# Motor_Control.net
KiCad netlist of a schematic drawn in Altium Designer
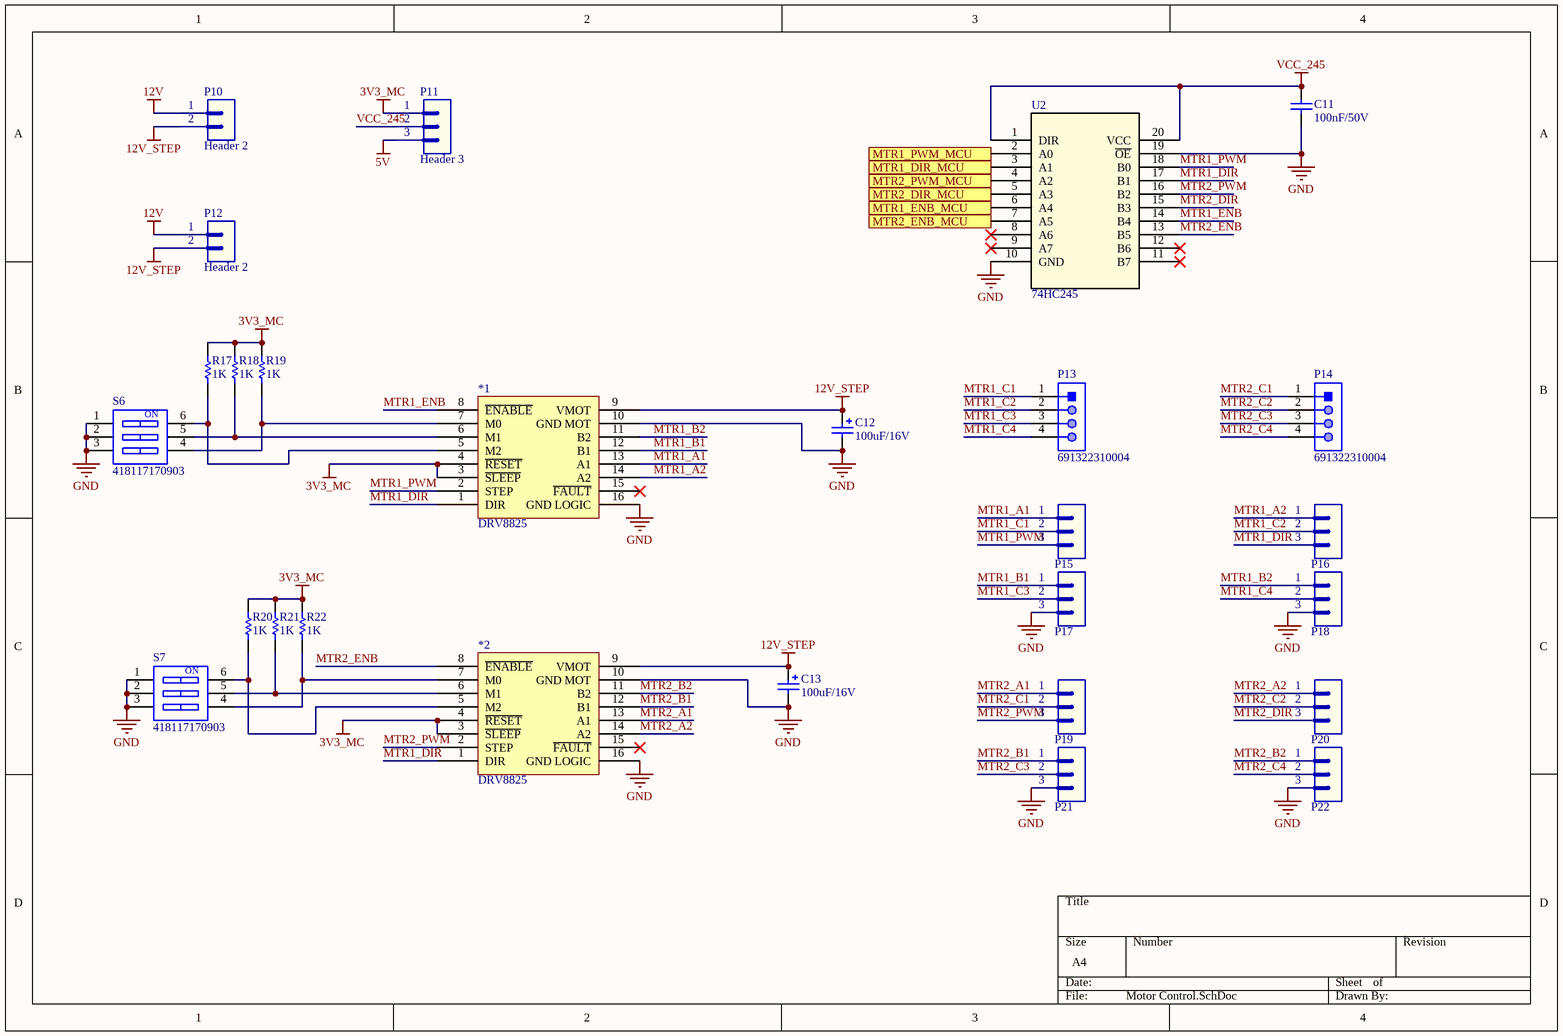
[diagram p0: Motor Control.SchDoc]

(export (version "E")
  (design (tool "Eeschema 10.0.6"))
  (components
    (comp (ref "*1")
      (value "DRV8825")
      (footprint "DRV8825")
      (libsource (lib "Integrated_Library") (part "DRV8825"))
    )
    (comp (ref "*2")
      (value "DRV8825")
      (footprint "DRV8825")
      (libsource (lib "Integrated_Library") (part "DRV8825"))
    )
    (comp (ref "C11")
      (value "100nF/50V")
      (footprint "CAP-SM-0805")
      (description "CAP CER 10UF 50V X5R 0805")
      (fields
        (field (name "MANUFACTURER") "Yageo")
        (field (name "MANUFACTURER PART NUMBER") "CC0805KKX5R9BB106")
      )
      (libsource (lib "Capacitor") (part "Cap-10uF-50V-0805"))
    )
    (comp (ref "C12")
      (value "100uF/16V")
      (footprint "CAP-SM-AL-SIZE-D-D6L6")
      (description "CAP ALUM 100UF 20% 16V SMD")
      (fields
        (field (name "MANUFACTURER") "Nichicon")
        (field (name "MANUFACTURER PART NUMBER") "UWX1C101MCL1GB")
      )
      (libsource (lib "Capacitor") (part "Cap-Al-100uF-16V-D6L5"))
    )
    (comp (ref "C13")
      (value "100uF/16V")
      (footprint "CAP-SM-AL-SIZE-D-D6L6")
      (description "CAP ALUM 100UF 20% 16V SMD")
      (fields
        (field (name "MANUFACTURER") "Nichicon")
        (field (name "MANUFACTURER PART NUMBER") "UWX1C101MCL1GB")
      )
      (libsource (lib "") (part "Cap-Al-100uF-16V-D6L5_1"))
    )
    (comp (ref "P10")
      (value "Header 2")
      (footprint "JP2")
      (description "Header, 2-Pin")
      (fields (field (name "PUBLISHER") "Altium Limited"))
      (libsource (lib "PIF_C16_lib") (part "Header 2"))
    )
    (comp (ref "P11")
      (value "Header 3")
      (footprint "JP3")
      (description "Header, 3-Pin")
      (fields (field (name "PUBLISHER") "Altium Limited"))
      (libsource (lib "PIF_C16_lib") (part "Header 3"))
    )
    (comp (ref "P12")
      (value "Header 2")
      (footprint "JP2")
      (description "Header, 2-Pin")
      (fields (field (name "PUBLISHER") "Altium Limited"))
      (libsource (lib "PIF_C16_lib") (part "Header 2"))
    )
    (comp (ref "P13")
      (value "691322310004")
      (footprint "691322310004")
      (description "WR-TBL Serie 322 Horizontal PCB Header, Pluggable, pitch 3.81mm, 4p")
      (fields (field (name "PUBLISHER") "Wurth Elektronik"))
      (libsource (lib "691101710002_Altium_WR-TBL_rev19a") (part "691322310004"))
    )
    (comp (ref "P14")
      (value "691322310004")
      (footprint "691322310004")
      (description "WR-TBL Serie 322 Horizontal PCB Header, Pluggable, pitch 3.81mm, 4p")
      (fields (field (name "PUBLISHER") "Wurth Elektronik"))
      (libsource (lib "691101710002_Altium_WR-TBL_rev19a") (part "691322310004"))
    )
    (comp (ref "P15")
      (value "Header 3")
      (footprint "JP3")
      (description "Header, 3-Pin")
      (fields (field (name "PUBLISHER") "Altium Limited"))
      (libsource (lib "Header-connector") (part "Header 3"))
    )
    (comp (ref "P16")
      (value "Header 3")
      (footprint "JP3")
      (description "Header, 3-Pin")
      (fields (field (name "PUBLISHER") "Altium Limited"))
      (libsource (lib "Header-connector") (part "Header 3"))
    )
    (comp (ref "P17")
      (value "Header 3")
      (footprint "JP3")
      (description "Header, 3-Pin")
      (fields (field (name "PUBLISHER") "Altium Limited"))
      (libsource (lib "Header-connector") (part "Header 3"))
    )
    (comp (ref "P18")
      (value "Header 3")
      (footprint "JP3")
      (description "Header, 3-Pin")
      (fields (field (name "PUBLISHER") "Altium Limited"))
      (libsource (lib "Header-connector") (part "Header 3"))
    )
    (comp (ref "P19")
      (value "Header 3")
      (footprint "JP3")
      (description "Header, 3-Pin")
      (fields (field (name "PUBLISHER") "Altium Limited"))
      (libsource (lib "Header-connector") (part "Header 3"))
    )
    (comp (ref "P20")
      (value "Header 3")
      (footprint "JP3")
      (description "Header, 3-Pin")
      (fields (field (name "PUBLISHER") "Altium Limited"))
      (libsource (lib "Header-connector") (part "Header 3"))
    )
    (comp (ref "P21")
      (value "Header 3")
      (footprint "JP3")
      (description "Header, 3-Pin")
      (fields (field (name "PUBLISHER") "Altium Limited"))
      (libsource (lib "Header-connector") (part "Header 3"))
    )
    (comp (ref "P22")
      (value "Header 3")
      (footprint "JP3")
      (description "Header, 3-Pin")
      (fields (field (name "PUBLISHER") "Altium Limited"))
      (libsource (lib "Header-connector") (part "Header 3"))
    )
    (comp (ref "R17")
      (value "1K")
      (footprint "Resistor:RES-SM-0805")
      (description "RES 1K OHM 1% 1/4W 0805")
      (fields
        (field (name "MANUFACTURER") "Stackpole Electronics Inc")
        (field (name "MANUFACTURER PART NUMBER") "RNCP0805FTD1K00")
      )
      (libsource (lib "Resistor") (part "Res-1K-0805"))
    )
    (comp (ref "R18")
      (value "1K")
      (footprint "Resistor:RES-SM-0805")
      (description "RES 1K OHM 1% 1/4W 0805")
      (fields
        (field (name "MANUFACTURER") "Stackpole Electronics Inc")
        (field (name "MANUFACTURER PART NUMBER") "RNCP0805FTD1K00")
      )
      (libsource (lib "Resistor") (part "Res-1K-0805"))
    )
    (comp (ref "R19")
      (value "1K")
      (footprint "Resistor:RES-SM-0805")
      (description "RES 1K OHM 1% 1/4W 0805")
      (fields
        (field (name "MANUFACTURER") "Stackpole Electronics Inc")
        (field (name "MANUFACTURER PART NUMBER") "RNCP0805FTD1K00")
      )
      (libsource (lib "Resistor") (part "Res-1K-0805"))
    )
    (comp (ref "R20")
      (value "1K")
      (footprint "Resistor:RES-SM-0805")
      (description "RES 1K OHM 1% 1/4W 0805")
      (fields
        (field (name "MANUFACTURER") "Stackpole Electronics Inc")
        (field (name "MANUFACTURER PART NUMBER") "RNCP0805FTD1K00")
      )
      (libsource (lib "Resistor") (part "Res-1K-0805"))
    )
    (comp (ref "R21")
      (value "1K")
      (footprint "Resistor:RES-SM-0805")
      (description "RES 1K OHM 1% 1/4W 0805")
      (fields
        (field (name "MANUFACTURER") "Stackpole Electronics Inc")
        (field (name "MANUFACTURER PART NUMBER") "RNCP0805FTD1K00")
      )
      (libsource (lib "Resistor") (part "Res-1K-0805"))
    )
    (comp (ref "R22")
      (value "1K")
      (footprint "Resistor:RES-SM-0805")
      (description "RES 1K OHM 1% 1/4W 0805")
      (fields
        (field (name "MANUFACTURER") "Stackpole Electronics Inc")
        (field (name "MANUFACTURER PART NUMBER") "RNCP0805FTD1K00")
      )
      (libsource (lib "Resistor") (part "Res-1K-0805"))
    )
    (comp (ref "S6")
      (value "418117170903")
      (footprint "418117170903")
      (description "WS-DITV Compact THT Dip Switch, Flat Actuator, pitch 2.54mm, 3p")
      (fields (field (name "PUBLISHER") "Wurth Elektronik"))
      (libsource (lib "418117170903_Altium_WS-DITV_rev19a") (part "418117170903"))
    )
    (comp (ref "S7")
      (value "418117170903")
      (footprint "418117170903")
      (description "WS-DITV Compact THT Dip Switch, Flat Actuator, pitch 2.54mm, 3p")
      (fields (field (name "PUBLISHER") "Wurth Elektronik"))
      (libsource (lib "418117170903_Altium_WS-DITV_rev19a") (part "418117170903"))
    )
    (comp (ref "U2")
      (value "74HC245")
      (footprint "74HC245,625")
      (description "No Description Available")
      (fields (field (name "COPYRIGHT") "Copyright (C) 2018 Accelerated Designs. All rights reserved"))
      (libsource (lib "Integrated_Library") (part "74HC245"))
    )
  )
  (nets
    (net (code "1") (name "/MTR1_A1") (class "Default")
      (node (ref "*1") (pin "13") (pinfunction "A1_13") (pintype "passive"))
      (node (ref "P15") (pin "1") (pinfunction "1_1") (pintype "passive"))
    )
    (net (code "2") (name "/MTR1_A2") (class "Default")
      (node (ref "*1") (pin "14") (pinfunction "A2_14") (pintype "passive"))
      (node (ref "P16") (pin "1") (pinfunction "1_1") (pintype "passive"))
    )
    (net (code "3") (name "/MTR1_B1") (class "Default")
      (node (ref "*1") (pin "12") (pinfunction "B1_12") (pintype "passive"))
      (node (ref "P17") (pin "1") (pinfunction "1_1") (pintype "passive"))
    )
    (net (code "4") (name "/MTR1_B2") (class "Default")
      (node (ref "*1") (pin "11") (pinfunction "B2_11") (pintype "passive"))
      (node (ref "P18") (pin "1") (pinfunction "1_1") (pintype "passive"))
    )
    (net (code "5") (name "/MTR1_C1") (class "Default")
      (node (ref "P13") (pin "1") (pinfunction "1_1") (pintype "passive"))
      (node (ref "P15") (pin "2") (pinfunction "2_2") (pintype "passive"))
    )
    (net (code "6") (name "/MTR1_C2") (class "Default")
      (node (ref "P13") (pin "2") (pinfunction "2_2") (pintype "passive"))
      (node (ref "P16") (pin "2") (pinfunction "2_2") (pintype "passive"))
    )
    (net (code "7") (name "/MTR1_C3") (class "Default")
      (node (ref "P13") (pin "3") (pinfunction "3_3") (pintype "passive"))
      (node (ref "P17") (pin "2") (pinfunction "2_2") (pintype "passive"))
    )
    (net (code "8") (name "/MTR1_C4") (class "Default")
      (node (ref "P13") (pin "4") (pinfunction "4_4") (pintype "passive"))
      (node (ref "P18") (pin "2") (pinfunction "2_2") (pintype "passive"))
    )
    (net (code "9") (name "/MTR1_DIR") (class "Default")
      (node (ref "*1") (pin "1") (pinfunction "DIR_1") (pintype "passive"))
      (node (ref "*2") (pin "1") (pinfunction "DIR_1") (pintype "passive"))
      (node (ref "P16") (pin "3") (pinfunction "3_3") (pintype "passive"))
      (node (ref "U2") (pin "17") (pinfunction "B1_17") (pintype "passive"))
    )
    (net (code "10") (name "/MTR1_DIR_MCU") (class "Default")
      (node (ref "U2") (pin "3") (pinfunction "A1_3") (pintype "passive"))
    )
    (net (code "11") (name "/MTR1_ENB") (class "Default")
      (node (ref "*1") (pin "8") (pinfunction "~{ENABLE}_8") (pintype "passive"))
      (node (ref "U2") (pin "14") (pinfunction "B4_14") (pintype "passive"))
    )
    (net (code "12") (name "/MTR1_ENB_MCU") (class "Default")
      (node (ref "U2") (pin "6") (pinfunction "A4_6") (pintype "passive"))
    )
    (net (code "13") (name "/MTR1_PWM") (class "Default")
      (node (ref "*1") (pin "2") (pinfunction "STEP_2") (pintype "passive"))
      (node (ref "P15") (pin "3") (pinfunction "3_3") (pintype "passive"))
      (node (ref "U2") (pin "18") (pinfunction "B0_18") (pintype "passive"))
    )
    (net (code "14") (name "/MTR1_PWM_MCU") (class "Default")
      (node (ref "U2") (pin "2") (pinfunction "A0_2") (pintype "passive"))
    )
    (net (code "15") (name "/MTR2_A1") (class "Default")
      (node (ref "*2") (pin "13") (pinfunction "A1_13") (pintype "passive"))
      (node (ref "P19") (pin "1") (pinfunction "1_1") (pintype "passive"))
    )
    (net (code "16") (name "/MTR2_A2") (class "Default")
      (node (ref "*2") (pin "14") (pinfunction "A2_14") (pintype "passive"))
      (node (ref "P20") (pin "1") (pinfunction "1_1") (pintype "passive"))
    )
    (net (code "17") (name "/MTR2_B1") (class "Default")
      (node (ref "*2") (pin "12") (pinfunction "B1_12") (pintype "passive"))
      (node (ref "P21") (pin "1") (pinfunction "1_1") (pintype "passive"))
    )
    (net (code "18") (name "/MTR2_B2") (class "Default")
      (node (ref "*2") (pin "11") (pinfunction "B2_11") (pintype "passive"))
      (node (ref "P22") (pin "1") (pinfunction "1_1") (pintype "passive"))
    )
    (net (code "19") (name "/MTR2_C1") (class "Default")
      (node (ref "P14") (pin "1") (pinfunction "1_1") (pintype "passive"))
      (node (ref "P19") (pin "2") (pinfunction "2_2") (pintype "passive"))
    )
    (net (code "20") (name "/MTR2_C2") (class "Default")
      (node (ref "P14") (pin "2") (pinfunction "2_2") (pintype "passive"))
      (node (ref "P20") (pin "2") (pinfunction "2_2") (pintype "passive"))
    )
    (net (code "21") (name "/MTR2_C3") (class "Default")
      (node (ref "P14") (pin "3") (pinfunction "3_3") (pintype "passive"))
      (node (ref "P21") (pin "2") (pinfunction "2_2") (pintype "passive"))
    )
    (net (code "22") (name "/MTR2_C4") (class "Default")
      (node (ref "P14") (pin "4") (pinfunction "4_4") (pintype "passive"))
      (node (ref "P22") (pin "2") (pinfunction "2_2") (pintype "passive"))
    )
    (net (code "23") (name "/MTR2_DIR") (class "Default")
      (node (ref "P20") (pin "3") (pinfunction "3_3") (pintype "passive"))
      (node (ref "U2") (pin "15") (pinfunction "B3_15") (pintype "passive"))
    )
    (net (code "24") (name "/MTR2_DIR_MCU") (class "Default")
      (node (ref "U2") (pin "5") (pinfunction "A3_5") (pintype "passive"))
    )
    (net (code "25") (name "/MTR2_ENB") (class "Default")
      (node (ref "*2") (pin "8") (pinfunction "~{ENABLE}_8") (pintype "passive"))
      (node (ref "U2") (pin "13") (pinfunction "B5_13") (pintype "passive"))
    )
    (net (code "26") (name "/MTR2_ENB_MCU") (class "Default")
      (node (ref "U2") (pin "7") (pinfunction "A5_7") (pintype "passive"))
    )
    (net (code "27") (name "/MTR2_PWM") (class "Default")
      (node (ref "*2") (pin "2") (pinfunction "STEP_2") (pintype "passive"))
      (node (ref "P19") (pin "3") (pinfunction "3_3") (pintype "passive"))
      (node (ref "U2") (pin "16") (pinfunction "B2_16") (pintype "passive"))
    )
    (net (code "28") (name "/MTR2_PWM_MCU") (class "Default")
      (node (ref "U2") (pin "4") (pinfunction "A2_4") (pintype "passive"))
    )
    (net (code "29") (name "3V3_MC") (class "Default")
      (node (ref "*1") (pin "3") (pinfunction "~{SLEEP}_3") (pintype "passive"))
      (node (ref "*1") (pin "4") (pinfunction "~{RESET}_4") (pintype "passive"))
      (node (ref "*2") (pin "3") (pinfunction "~{SLEEP}_3") (pintype "passive"))
      (node (ref "*2") (pin "4") (pinfunction "~{RESET}_4") (pintype "passive"))
      (node (ref "P11") (pin "1") (pinfunction "1_1") (pintype "passive"))
      (node (ref "R17") (pin "2") (pinfunction "2_2") (pintype "passive"))
      (node (ref "R18") (pin "2") (pinfunction "2_2") (pintype "passive"))
      (node (ref "R19") (pin "2") (pinfunction "2_2") (pintype "passive"))
      (node (ref "R20") (pin "2") (pinfunction "2_2") (pintype "passive"))
      (node (ref "R21") (pin "2") (pinfunction "2_2") (pintype "passive"))
      (node (ref "R22") (pin "2") (pinfunction "2_2") (pintype "passive"))
    )
    (net (code "30") (name "5V") (class "Default")
      (node (ref "P11") (pin "3") (pinfunction "3_3") (pintype "passive"))
    )
    (net (code "31") (name "12V") (class "Default")
      (node (ref "P10") (pin "1") (pinfunction "1_1") (pintype "passive"))
      (node (ref "P12") (pin "1") (pinfunction "1_1") (pintype "passive"))
    )
    (net (code "32") (name "12V_STEP") (class "Default")
      (node (ref "*1") (pin "9") (pinfunction "VMOT_9") (pintype "passive"))
      (node (ref "*2") (pin "9") (pinfunction "VMOT_9") (pintype "passive"))
      (node (ref "C12") (pin "1") (pinfunction "1_1") (pintype "passive"))
      (node (ref "C13") (pin "2") (pinfunction "2_2") (pintype "passive"))
      (node (ref "P10") (pin "2") (pinfunction "2_2") (pintype "passive"))
      (node (ref "P12") (pin "2") (pinfunction "2_2") (pintype "passive"))
    )
    (net (code "33") (name "GND") (class "Default")
      (node (ref "*1") (pin "10") (pinfunction "GND_MOT_10") (pintype "passive"))
      (node (ref "*1") (pin "16") (pinfunction "GND_LOGIC_16") (pintype "passive"))
      (node (ref "*2") (pin "10") (pinfunction "GND_MOT_10") (pintype "passive"))
      (node (ref "*2") (pin "16") (pinfunction "GND_LOGIC_16") (pintype "passive"))
      (node (ref "C11") (pin "1") (pinfunction "1_1") (pintype "passive"))
      (node (ref "C12") (pin "2") (pinfunction "2_2") (pintype "passive"))
      (node (ref "C13") (pin "1") (pinfunction "1_1") (pintype "passive"))
      (node (ref "P17") (pin "3") (pinfunction "3_3") (pintype "passive"))
      (node (ref "P18") (pin "3") (pinfunction "3_3") (pintype "passive"))
      (node (ref "P21") (pin "3") (pinfunction "3_3") (pintype "passive"))
      (node (ref "P22") (pin "3") (pinfunction "3_3") (pintype "passive"))
      (node (ref "S6") (pin "1") (pinfunction "1_1") (pintype "passive"))
      (node (ref "S6") (pin "2") (pinfunction "2_2") (pintype "passive"))
      (node (ref "S6") (pin "3") (pinfunction "3_3") (pintype "passive"))
      (node (ref "S7") (pin "1") (pinfunction "1_1") (pintype "passive"))
      (node (ref "S7") (pin "2") (pinfunction "2_2") (pintype "passive"))
      (node (ref "S7") (pin "3") (pinfunction "3_3") (pintype "passive"))
      (node (ref "U2") (pin "10") (pinfunction "GND_10") (pintype "passive"))
      (node (ref "U2") (pin "19") (pinfunction "~{OE}_19") (pintype "passive"))
    )
    (net (code "34") (name "Net-(*1-M0)") (class "Default")
      (node (ref "*1") (pin "7") (pinfunction "M0_7") (pintype "passive"))
      (node (ref "R19") (pin "1") (pinfunction "1_1") (pintype "passive"))
      (node (ref "S6") (pin "4") (pinfunction "4_4") (pintype "passive"))
    )
    (net (code "35") (name "Net-(*1-M1)") (class "Default")
      (node (ref "*1") (pin "6") (pinfunction "M1_6") (pintype "passive"))
      (node (ref "R18") (pin "1") (pinfunction "1_1") (pintype "passive"))
      (node (ref "S6") (pin "5") (pinfunction "5_5") (pintype "passive"))
    )
    (net (code "36") (name "Net-(*1-M2)") (class "Default")
      (node (ref "*1") (pin "5") (pinfunction "M2_5") (pintype "passive"))
      (node (ref "R17") (pin "1") (pinfunction "1_1") (pintype "passive"))
      (node (ref "S6") (pin "6") (pinfunction "6_6") (pintype "passive"))
    )
    (net (code "37") (name "Net-(*2-M0)") (class "Default")
      (node (ref "*2") (pin "7") (pinfunction "M0_7") (pintype "passive"))
      (node (ref "R22") (pin "1") (pinfunction "1_1") (pintype "passive"))
      (node (ref "S7") (pin "4") (pinfunction "4_4") (pintype "passive"))
    )
    (net (code "38") (name "Net-(*2-M1)") (class "Default")
      (node (ref "*2") (pin "6") (pinfunction "M1_6") (pintype "passive"))
      (node (ref "R21") (pin "1") (pinfunction "1_1") (pintype "passive"))
      (node (ref "S7") (pin "5") (pinfunction "5_5") (pintype "passive"))
    )
    (net (code "39") (name "Net-(*2-M2)") (class "Default")
      (node (ref "*2") (pin "5") (pinfunction "M2_5") (pintype "passive"))
      (node (ref "R20") (pin "1") (pinfunction "1_1") (pintype "passive"))
      (node (ref "S7") (pin "6") (pinfunction "6_6") (pintype "passive"))
    )
    (net (code "40") (name "VCC_245") (class "Default")
      (node (ref "C11") (pin "2") (pinfunction "2_2") (pintype "passive"))
      (node (ref "P11") (pin "2") (pinfunction "2_2") (pintype "passive"))
      (node (ref "U2") (pin "1") (pinfunction "DIR_1") (pintype "passive"))
      (node (ref "U2") (pin "20") (pinfunction "VCC_20") (pintype "passive"))
    )
    (net (code "41") (name "unconnected-(*1-~{FAULT}-Pad15)") (class "Default")
      (node (ref "*1") (pin "15") (pinfunction "~{FAULT}_15") (pintype "passive+no_connect"))
    )
    (net (code "42") (name "unconnected-(*2-~{FAULT}-Pad15)") (class "Default")
      (node (ref "*2") (pin "15") (pinfunction "~{FAULT}_15") (pintype "passive+no_connect"))
    )
    (net (code "43") (name "unconnected-(U2-A6-Pad8)") (class "Default")
      (node (ref "U2") (pin "8") (pinfunction "A6_8") (pintype "passive+no_connect"))
    )
    (net (code "44") (name "unconnected-(U2-A7-Pad9)") (class "Default")
      (node (ref "U2") (pin "9") (pinfunction "A7_9") (pintype "passive+no_connect"))
    )
    (net (code "45") (name "unconnected-(U2-B6-Pad12)") (class "Default")
      (node (ref "U2") (pin "12") (pinfunction "B6_12") (pintype "passive+no_connect"))
    )
    (net (code "46") (name "unconnected-(U2-B7-Pad11)") (class "Default")
      (node (ref "U2") (pin "11") (pinfunction "B7_11") (pintype "passive+no_connect"))
    )
  )
)
